# 150225_AriloTX_REV2_4_0_868MHZ.net
KiCad netlist of a schematic drawn in EAGLE
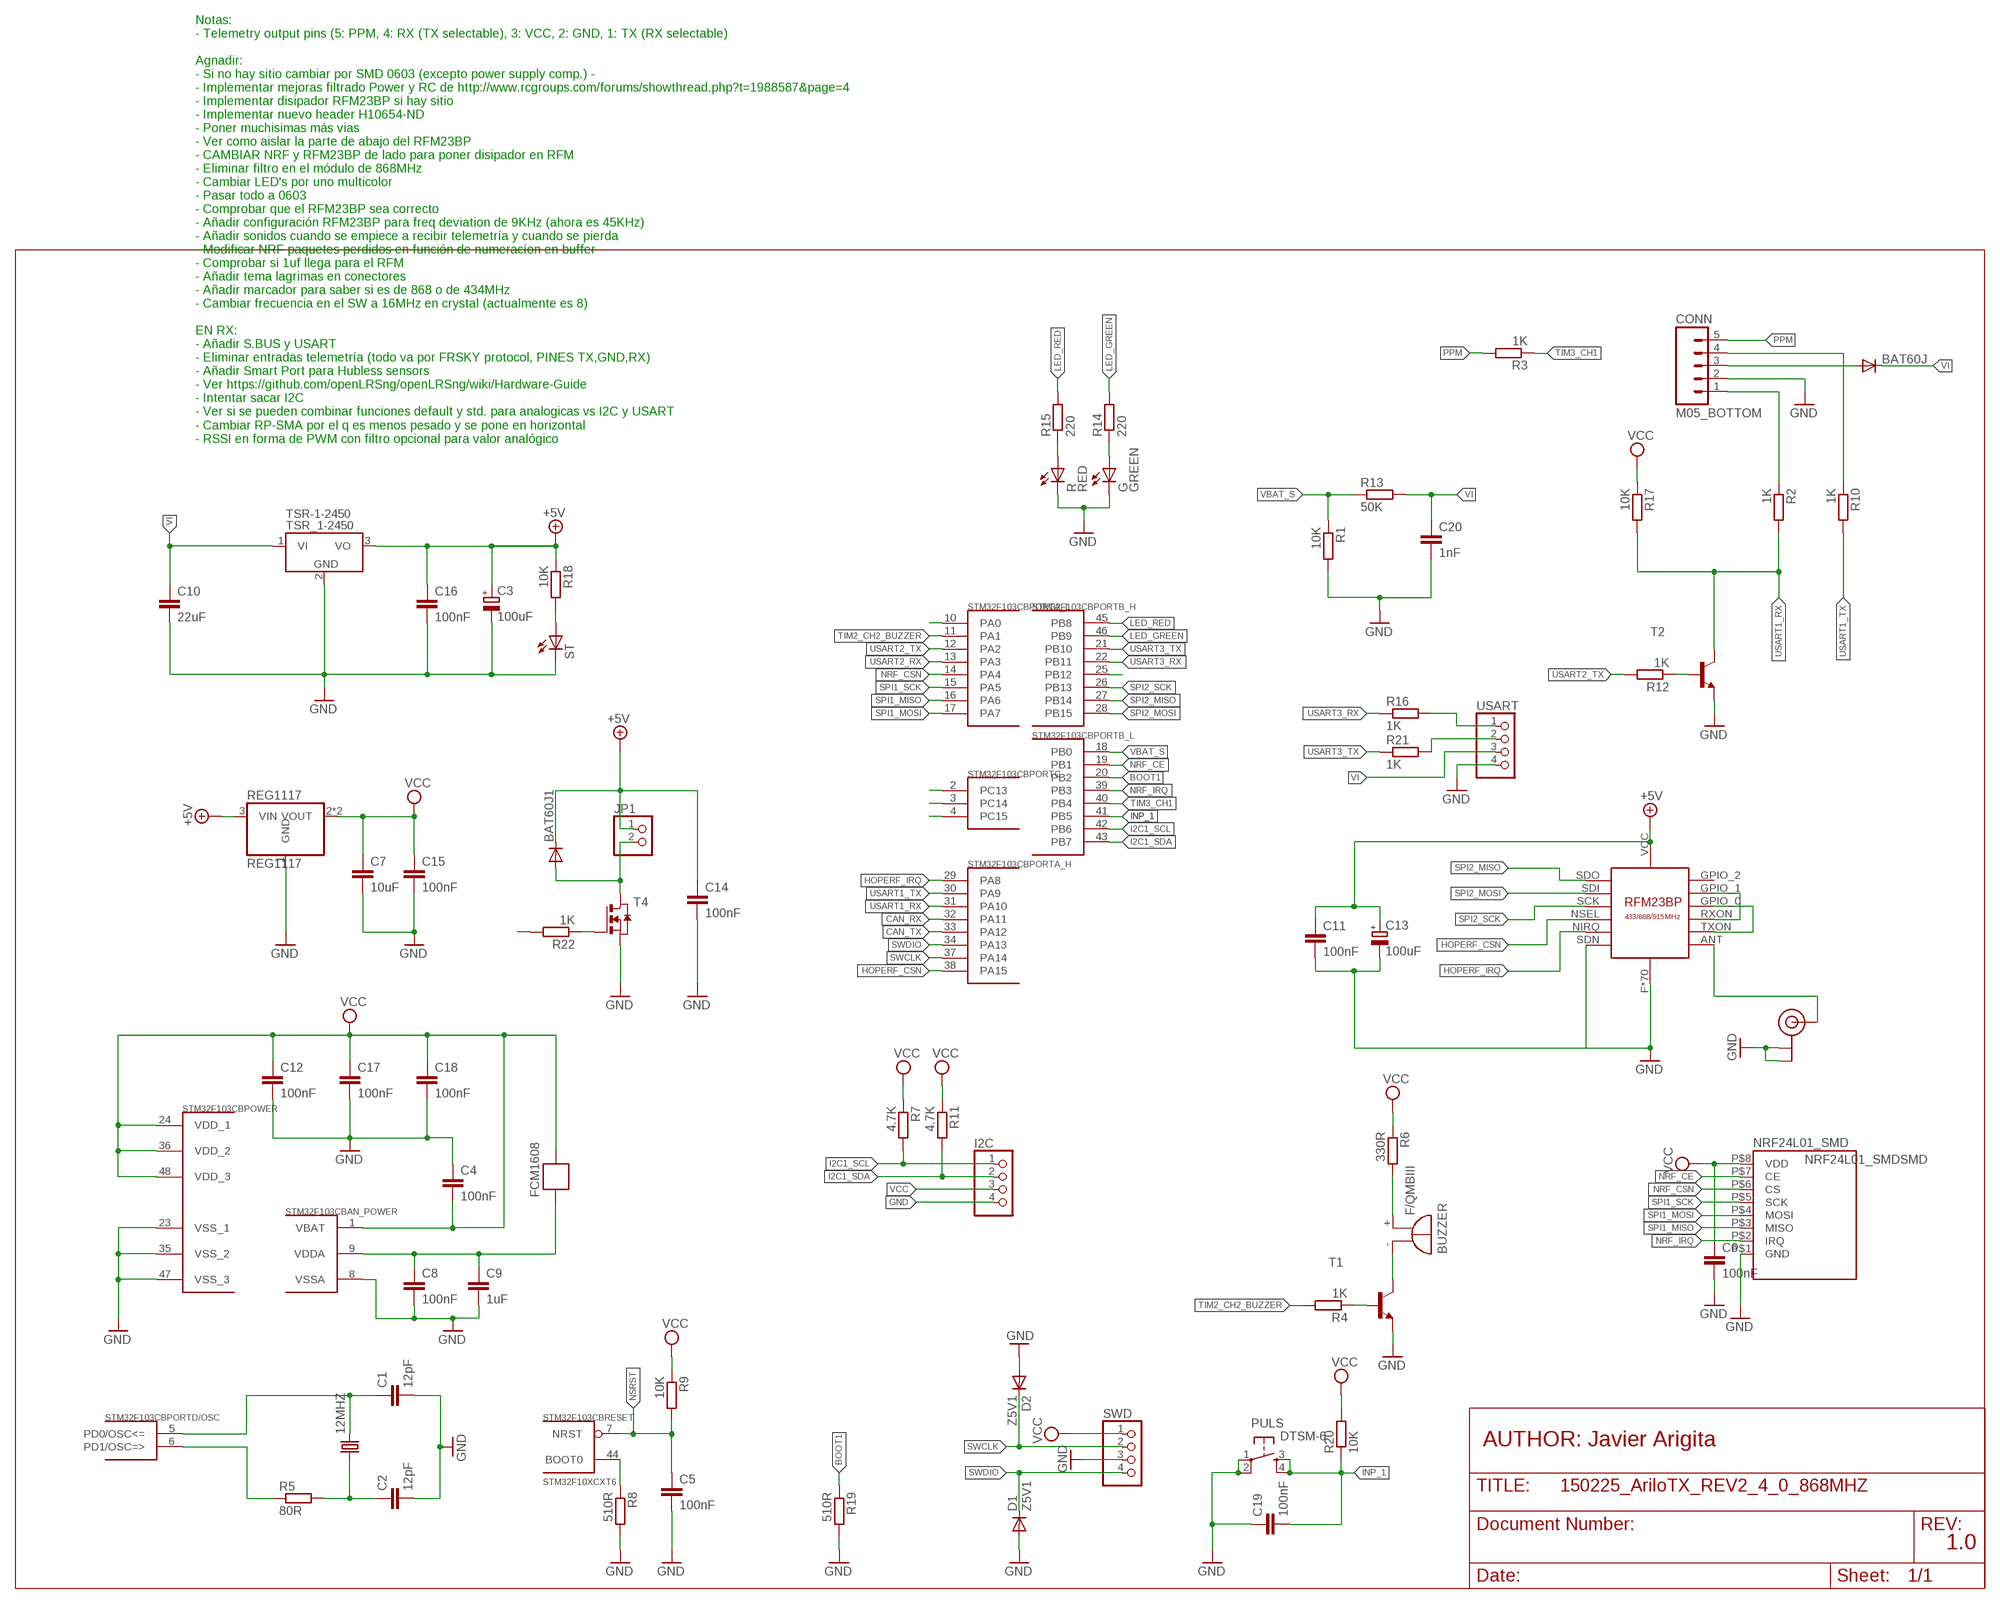
[diagram p0: schematic, sheet 1]

(export (version "E")
  (design (tool "Eeschema 10.0.6"))
  (components
    (comp (ref "12MHZ")
      (value "CRYSTAL5X3")
      (footprint "eagle-import:CRYSTAL-SMD-5X3")
      (libsource (lib "eagle-import") (part "CRYSTAL5X3"))
    )
    (comp (ref "BAT60J")
      (value "DIODE-SOD323-R")
      (footprint "eagle-import:SOD323-R")
      (libsource (lib "eagle-import") (part "DIODE-SOD323-R"))
    )
    (comp (ref "BAT60J1")
      (value "DIODE-SOD323-R")
      (footprint "eagle-import:SOD323-R")
      (libsource (lib "eagle-import") (part "DIODE-SOD323-R"))
    )
    (comp (ref "BUZZER")
      (value "F/QMBIII")
      (footprint "eagle-import:F_QMBIII")
      (libsource (lib "eagle-import") (part "F/QMBIII"))
    )
    (comp (ref "C1")
      (value "12pF")
      (footprint "eagle-import:C0603")
      (libsource (lib "eagle-import") (part "C-EUC0603"))
    )
    (comp (ref "C2")
      (value "12pF")
      (footprint "eagle-import:C0603")
      (libsource (lib "eagle-import") (part "C-EUC0603"))
    )
    (comp (ref "C3")
      (value "100uF")
      (footprint "eagle-import:SMC_B")
      (libsource (lib "eagle-import") (part "CPOL-EUSMCB"))
    )
    (comp (ref "C4")
      (value "100nF")
      (footprint "eagle-import:C0603")
      (libsource (lib "eagle-import") (part "C-EUC0603"))
    )
    (comp (ref "C5")
      (value "100nF")
      (footprint "eagle-import:C0603")
      (libsource (lib "eagle-import") (part "C-EUC0603"))
    )
    (comp (ref "C6")
      (value "100nF")
      (footprint "eagle-import:C0603")
      (libsource (lib "eagle-import") (part "C-EUC0603"))
    )
    (comp (ref "C7")
      (value "10uF")
      (footprint "eagle-import:C0805")
      (libsource (lib "eagle-import") (part "C-EUC0805"))
    )
    (comp (ref "C8")
      (value "100nF")
      (footprint "eagle-import:C0603")
      (libsource (lib "eagle-import") (part "C-EUC0603"))
    )
    (comp (ref "C9")
      (value "1uF")
      (footprint "eagle-import:C0603")
      (libsource (lib "eagle-import") (part "C-EUC0603"))
    )
    (comp (ref "C10")
      (value "22uF")
      (footprint "eagle-import:C3216")
      (libsource (lib "eagle-import") (part "resistor_C-EUC3216"))
    )
    (comp (ref "C11")
      (value "100nF")
      (footprint "eagle-import:C0603")
      (libsource (lib "eagle-import") (part "C-EUC0603"))
    )
    (comp (ref "C12")
      (value "100nF")
      (footprint "eagle-import:C0603")
      (libsource (lib "eagle-import") (part "C-EUC0603"))
    )
    (comp (ref "C13")
      (value "100uF")
      (footprint "eagle-import:SMC_B")
      (libsource (lib "eagle-import") (part "CPOL-EUSMCB"))
    )
    (comp (ref "C14")
      (value "100nF")
      (footprint "eagle-import:C0603")
      (libsource (lib "eagle-import") (part "C-EUC0603"))
    )
    (comp (ref "C15")
      (value "100nF")
      (footprint "eagle-import:C0603")
      (libsource (lib "eagle-import") (part "C-EUC0603"))
    )
    (comp (ref "C16")
      (value "100nF")
      (footprint "eagle-import:C0603")
      (libsource (lib "eagle-import") (part "C-EUC0603"))
    )
    (comp (ref "C17")
      (value "100nF")
      (footprint "eagle-import:C0603")
      (libsource (lib "eagle-import") (part "C-EUC0603"))
    )
    (comp (ref "C18")
      (value "100nF")
      (footprint "eagle-import:C0603")
      (libsource (lib "eagle-import") (part "C-EUC0603"))
    )
    (comp (ref "C19")
      (value "100nF")
      (footprint "eagle-import:C0603")
      (libsource (lib "eagle-import") (part "C-EUC0603"))
    )
    (comp (ref "C20")
      (value "1nF")
      (footprint "eagle-import:C0603")
      (libsource (lib "eagle-import") (part "C-EUC0603"))
    )
    (comp (ref "CONN")
      (value "M05_BOTTOM")
      (footprint "eagle-import:M05_BOTTOM")
      (libsource (lib "eagle-import") (part "M05_BOTTOM"))
    )
    (comp (ref "D1")
      (value "Z5V1")
      (footprint "eagle-import:SOD323-R")
      (libsource (lib "eagle-import") (part "DIODE-SOD323-R"))
    )
    (comp (ref "D2")
      (value "Z5V1")
      (footprint "eagle-import:SOD323-R")
      (libsource (lib "eagle-import") (part "DIODE-SOD323-R"))
    )
    (comp (ref "FCM1608")
      (value "FERRITE-BEAD")
      (footprint "eagle-import:R0603")
      (libsource (lib "eagle-import") (part "FERRITE-BEAD"))
    )
    (comp (ref "G")
      (value "GREEN")
      (footprint "eagle-import:CHIP-LED0603")
      (libsource (lib "eagle-import") (part "LEDCHIP-LED0603"))
    )
    (comp (ref "I2C")
      (value "PINHD-1X4")
      (footprint "eagle-import:1X04")
      (libsource (lib "eagle-import") (part "PINHD-1X4"))
    )
    (comp (ref "JP1")
      (value "PINHD-1X2")
      (footprint "eagle-import:1X02")
      (libsource (lib "eagle-import") (part "PINHD-1X2"))
    )
    (comp (ref "NRF24L01_SMD")
      (value "NRF24L01_SMDSMD")
      (footprint "eagle-import:NRF24L01_SMD")
      (libsource (lib "eagle-import") (part "NRF24L01_SMDSMD"))
    )
    (comp (ref "PULS")
      (value "DTSM-6")
      (footprint "eagle-import:DTSM-6")
      (libsource (lib "eagle-import") (part "DTSM-6"))
    )
    (comp (ref "R")
      (value "RED")
      (footprint "eagle-import:CHIP-LED0603")
      (libsource (lib "eagle-import") (part "LEDCHIP-LED0603"))
    )
    (comp (ref "R1")
      (value "10K")
      (footprint "eagle-import:R0603")
      (libsource (lib "eagle-import") (part "R-EU_R0603"))
    )
    (comp (ref "R2")
      (value "1K")
      (footprint "eagle-import:R0603")
      (libsource (lib "eagle-import") (part "R-EU_R0603"))
    )
    (comp (ref "R3")
      (value "1K")
      (footprint "eagle-import:R0603")
      (libsource (lib "eagle-import") (part "R-EU_R0603"))
    )
    (comp (ref "R4")
      (value "1K")
      (footprint "eagle-import:R0603")
      (libsource (lib "eagle-import") (part "R-EU_R0603"))
    )
    (comp (ref "R5")
      (value "80R")
      (footprint "eagle-import:R0603")
      (libsource (lib "eagle-import") (part "R-EU_R0603"))
    )
    (comp (ref "R6")
      (value "330R")
      (footprint "eagle-import:R0603")
      (libsource (lib "eagle-import") (part "R-EU_R0603"))
    )
    (comp (ref "R7")
      (value "4.7K")
      (footprint "eagle-import:R0603")
      (libsource (lib "eagle-import") (part "R-EU_R0603"))
    )
    (comp (ref "R8")
      (value "510R")
      (footprint "eagle-import:R0603")
      (libsource (lib "eagle-import") (part "R-EU_R0603"))
    )
    (comp (ref "R9")
      (value "10K")
      (footprint "eagle-import:R0603")
      (libsource (lib "eagle-import") (part "R-EU_R0603"))
    )
    (comp (ref "R10")
      (value "1K")
      (footprint "eagle-import:R0603")
      (libsource (lib "eagle-import") (part "R-EU_R0603"))
    )
    (comp (ref "R11")
      (value "4.7K")
      (footprint "eagle-import:R0603")
      (libsource (lib "eagle-import") (part "R-EU_R0603"))
    )
    (comp (ref "R12")
      (value "1K")
      (footprint "eagle-import:R0603")
      (libsource (lib "eagle-import") (part "R-EU_R0603"))
    )
    (comp (ref "R13")
      (value "50K")
      (footprint "eagle-import:R0603")
      (libsource (lib "eagle-import") (part "R-EU_R0603"))
    )
    (comp (ref "R14")
      (value "220")
      (footprint "eagle-import:R0603")
      (libsource (lib "eagle-import") (part "R-EU_R0603"))
    )
    (comp (ref "R15")
      (value "220")
      (footprint "eagle-import:R0603")
      (libsource (lib "eagle-import") (part "R-EU_R0603"))
    )
    (comp (ref "R16")
      (value "1K")
      (footprint "eagle-import:R0603")
      (libsource (lib "eagle-import") (part "R-EU_R0603"))
    )
    (comp (ref "R17")
      (value "10K")
      (footprint "eagle-import:R0603")
      (libsource (lib "eagle-import") (part "R-EU_R0603"))
    )
    (comp (ref "R18")
      (value "10K")
      (footprint "eagle-import:R0603")
      (libsource (lib "eagle-import") (part "R-EU_R0603"))
    )
    (comp (ref "R19")
      (value "510R")
      (footprint "eagle-import:R0603")
      (libsource (lib "eagle-import") (part "R-EU_R0603"))
    )
    (comp (ref "R20")
      (value "10K")
      (footprint "eagle-import:R0603")
      (libsource (lib "eagle-import") (part "R-EU_R0603"))
    )
    (comp (ref "R21")
      (value "1K")
      (footprint "eagle-import:R0603")
      (libsource (lib "eagle-import") (part "R-EU_R0603"))
    )
    (comp (ref "R22")
      (value "1K")
      (footprint "eagle-import:R0603")
      (libsource (lib "eagle-import") (part "R-EU_R0603"))
    )
    (comp (ref "REG1117")
      (value "REG1117")
      (footprint "eagle-import:SOT223")
      (libsource (lib "eagle-import") (part "REG1117"))
    )
    (comp (ref "ST")
      (value "LEDCHIP-LED0603")
      (footprint "eagle-import:CHIP-LED0603")
      (libsource (lib "eagle-import") (part "LEDCHIP-LED0603"))
    )
    (comp (ref "STM32F103CB")
      (value "STM32F10XCXT6")
      (footprint "eagle-import:TQFP48")
      (libsource (lib "eagle-import") (part "STM32F10XCXT6"))
    )
    (comp (ref "SWD")
      (value "PINHD-1X4")
      (footprint "eagle-import:1X04")
      (libsource (lib "eagle-import") (part "PINHD-1X4"))
    )
    (comp (ref "T1")
      (value "BC848-NPN-SOT23-BEC")
      (footprint "eagle-import:SOT23-BEC")
      (libsource (lib "eagle-import") (part "-NPN-SOT23-BECBC848"))
    )
    (comp (ref "T2")
      (value "BC848-NPN-SOT23-BEC")
      (footprint "eagle-import:SOT23-BEC")
      (libsource (lib "eagle-import") (part "-NPN-SOT23-BECBC848"))
    )
    (comp (ref "T4")
      (value "NMOSSOT23")
      (footprint "eagle-import:SOT-23")
      (libsource (lib "eagle-import") (part "NMOSSOT23"))
    )
    (comp (ref "TSR-1-2450")
      (value "TSR_1-2450")
      (footprint "eagle-import:TSR-1")
      (libsource (lib "eagle-import") (part "TSR_1-2450"))
    )
    (comp (ref "U$1")
      (value "RFM23BP")
      (footprint "eagle-import:RFM23BP")
      (libsource (lib "eagle-import") (part "RFM23BP"))
    )
    (comp (ref "U.FL")
      (value "U.FL")
      (footprint "eagle-import:U.FL")
      (libsource (lib "eagle-import") (part "U.FL"))
    )
    (comp (ref "USART")
      (value "PINHD-1X4")
      (footprint "eagle-import:1X04")
      (libsource (lib "eagle-import") (part "PINHD-1X4"))
    )
  )
  (nets
    (net (code "1") (name "+5V") (class "Default")
      (node (ref "BAT60J1") (pin "C") (pinfunction "C_C") (pintype "passive"))
      (node (ref "C11") (pin "1") (pinfunction "1_1") (pintype "passive"))
      (node (ref "C13") (pin "+") (pinfunction "+_+") (pintype "passive"))
      (node (ref "C14") (pin "1") (pinfunction "1_1") (pintype "passive"))
      (node (ref "C16") (pin "1") (pinfunction "1_1") (pintype "passive"))
      (node (ref "C3") (pin "+") (pinfunction "+_+") (pintype "passive"))
      (node (ref "JP1") (pin "1") (pinfunction "1_1") (pintype "passive"))
      (node (ref "R18") (pin "1") (pinfunction "1_1") (pintype "passive"))
      (node (ref "REG1117") (pin "3") (pinfunction "VIN_3") (pintype "input"))
      (node (ref "TSR-1-2450") (pin "3") (pinfunction "VO_3") (pintype "power_in"))
      (node (ref "U$1") (pin "VCC") (pinfunction "VCC_VCC") (pintype "power_in"))
    )
    (net (code "2") (name "BOOT1") (class "Default")
      (node (ref "R19") (pin "1") (pinfunction "1_1") (pintype "passive"))
      (node (ref "STM32F103CB") (pin "20") (pinfunction "PB2_20") (pintype "bidirectional"))
    )
    (net (code "3") (name "CAN_RX") (class "Default")
      (node (ref "STM32F103CB") (pin "32") (pinfunction "PA11_32") (pintype "bidirectional"))
    )
    (net (code "4") (name "CAN_TX") (class "Default")
      (node (ref "STM32F103CB") (pin "33") (pinfunction "PA12_33") (pintype "bidirectional"))
    )
    (net (code "5") (name "GND") (class "Default")
      (node (ref "C1") (pin "2") (pinfunction "2_2") (pintype "passive"))
      (node (ref "C10") (pin "2") (pinfunction "2_2") (pintype "passive"))
      (node (ref "C11") (pin "2") (pinfunction "2_2") (pintype "passive"))
      (node (ref "C12") (pin "2") (pinfunction "2_2") (pintype "passive"))
      (node (ref "C13") (pin "-") (pinfunction "-_-") (pintype "passive"))
      (node (ref "C14") (pin "2") (pinfunction "2_2") (pintype "passive"))
      (node (ref "C15") (pin "2") (pinfunction "2_2") (pintype "passive"))
      (node (ref "C16") (pin "2") (pinfunction "2_2") (pintype "passive"))
      (node (ref "C17") (pin "2") (pinfunction "2_2") (pintype "passive"))
      (node (ref "C18") (pin "2") (pinfunction "2_2") (pintype "passive"))
      (node (ref "C19") (pin "1") (pinfunction "1_1") (pintype "passive"))
      (node (ref "C2") (pin "2") (pinfunction "2_2") (pintype "passive"))
      (node (ref "C20") (pin "2") (pinfunction "2_2") (pintype "passive"))
      (node (ref "C3") (pin "-") (pinfunction "-_-") (pintype "passive"))
      (node (ref "C4") (pin "1") (pinfunction "1_1") (pintype "passive"))
      (node (ref "C5") (pin "2") (pinfunction "2_2") (pintype "passive"))
      (node (ref "C6") (pin "2") (pinfunction "2_2") (pintype "passive"))
      (node (ref "C7") (pin "2") (pinfunction "2_2") (pintype "passive"))
      (node (ref "C8") (pin "2") (pinfunction "2_2") (pintype "passive"))
      (node (ref "C9") (pin "2") (pinfunction "2_2") (pintype "passive"))
      (node (ref "CONN") (pin "2") (pinfunction "2_2") (pintype "passive"))
      (node (ref "D1") (pin "A") (pinfunction "A_A") (pintype "passive"))
      (node (ref "D2") (pin "A") (pinfunction "A_A") (pintype "passive"))
      (node (ref "G") (pin "C") (pinfunction "C_C") (pintype "passive"))
      (node (ref "I2C") (pin "4") (pinfunction "4_4") (pintype "passive"))
      (node (ref "NRF24L01_SMD") (pin "P$1") (pinfunction "GND_P$1") (pintype "power_in"))
      (node (ref "PULS") (pin "1") (pinfunction "1_1") (pintype "passive"))
      (node (ref "PULS") (pin "2") (pinfunction "2_2") (pintype "passive"))
      (node (ref "R") (pin "C") (pinfunction "C_C") (pintype "passive"))
      (node (ref "R1") (pin "2") (pinfunction "2_2") (pintype "passive"))
      (node (ref "R19") (pin "2") (pinfunction "2_2") (pintype "passive"))
      (node (ref "R8") (pin "2") (pinfunction "2_2") (pintype "passive"))
      (node (ref "REG1117") (pin "1") (pinfunction "GND_1") (pintype "power_in"))
      (node (ref "ST") (pin "C") (pinfunction "C_C") (pintype "passive"))
      (node (ref "STM32F103CB") (pin "23") (pinfunction "VSS_1_23") (pintype "power_in"))
      (node (ref "STM32F103CB") (pin "35") (pinfunction "VSS_2_35") (pintype "power_in"))
      (node (ref "STM32F103CB") (pin "47") (pinfunction "VSS_3_47") (pintype "power_in"))
      (node (ref "STM32F103CB") (pin "8") (pinfunction "VSSA_8") (pintype "power_in"))
      (node (ref "SWD") (pin "3") (pinfunction "3_3") (pintype "passive"))
      (node (ref "T1") (pin "E") (pinfunction "E_E") (pintype "passive"))
      (node (ref "T2") (pin "E") (pinfunction "E_E") (pintype "passive"))
      (node (ref "T4") (pin "2") (pinfunction "S_2") (pintype "passive"))
      (node (ref "TSR-1-2450") (pin "2") (pinfunction "GND_2") (pintype "power_in"))
      (node (ref "U$1") (pin "F") (pinfunction "GND_F") (pintype "power_in"))
      (node (ref "U$1") (pin "F1") (pinfunction "GND_F1") (pintype "power_in"))
      (node (ref "U$1") (pin "F10") (pinfunction "GND_F10") (pintype "power_in"))
      (node (ref "U$1") (pin "F11") (pinfunction "GND_F11") (pintype "power_in"))
      (node (ref "U$1") (pin "F12") (pinfunction "GND_F12") (pintype "power_in"))
      (node (ref "U$1") (pin "F13") (pinfunction "GND_F13") (pintype "power_in"))
      (node (ref "U$1") (pin "F14") (pinfunction "GND_F14") (pintype "power_in"))
      (node (ref "U$1") (pin "F15") (pinfunction "GND_F15") (pintype "power_in"))
      (node (ref "U$1") (pin "F16") (pinfunction "GND_F16") (pintype "power_in"))
      (node (ref "U$1") (pin "F17") (pinfunction "GND_F17") (pintype "power_in"))
      (node (ref "U$1") (pin "F18") (pinfunction "GND_F18") (pintype "power_in"))
      (node (ref "U$1") (pin "F19") (pinfunction "GND_F19") (pintype "power_in"))
      (node (ref "U$1") (pin "F2") (pinfunction "GND_F2") (pintype "power_in"))
      (node (ref "U$1") (pin "F20") (pinfunction "GND_F20") (pintype "power_in"))
      (node (ref "U$1") (pin "F21") (pinfunction "GND_F21") (pintype "power_in"))
      (node (ref "U$1") (pin "F22") (pinfunction "GND_F22") (pintype "power_in"))
      (node (ref "U$1") (pin "F23") (pinfunction "GND_F23") (pintype "power_in"))
      (node (ref "U$1") (pin "F24") (pinfunction "GND_F24") (pintype "power_in"))
      (node (ref "U$1") (pin "F25") (pinfunction "GND_F25") (pintype "power_in"))
      (node (ref "U$1") (pin "F26") (pinfunction "GND_F26") (pintype "power_in"))
      (node (ref "U$1") (pin "F27") (pinfunction "GND_F27") (pintype "power_in"))
      (node (ref "U$1") (pin "F28") (pinfunction "GND_F28") (pintype "power_in"))
      (node (ref "U$1") (pin "F29") (pinfunction "GND_F29") (pintype "power_in"))
      (node (ref "U$1") (pin "F3") (pinfunction "GND_F3") (pintype "power_in"))
      (node (ref "U$1") (pin "F30") (pinfunction "GND_F30") (pintype "power_in"))
      (node (ref "U$1") (pin "F31") (pinfunction "GND_F31") (pintype "power_in"))
      (node (ref "U$1") (pin "F32") (pinfunction "GND_F32") (pintype "power_in"))
      (node (ref "U$1") (pin "F33") (pinfunction "GND_F33") (pintype "power_in"))
      (node (ref "U$1") (pin "F34") (pinfunction "GND_F34") (pintype "power_in"))
      (node (ref "U$1") (pin "F35") (pinfunction "GND_F35") (pintype "power_in"))
      (node (ref "U$1") (pin "F36") (pinfunction "GND_F36") (pintype "power_in"))
      (node (ref "U$1") (pin "F37") (pinfunction "GND_F37") (pintype "power_in"))
      (node (ref "U$1") (pin "F38") (pinfunction "GND_F38") (pintype "power_in"))
      (node (ref "U$1") (pin "F39") (pinfunction "GND_F39") (pintype "power_in"))
      (node (ref "U$1") (pin "F4") (pinfunction "GND_F4") (pintype "power_in"))
      (node (ref "U$1") (pin "F40") (pinfunction "GND_F40") (pintype "power_in"))
      (node (ref "U$1") (pin "F41") (pinfunction "GND_F41") (pintype "power_in"))
      (node (ref "U$1") (pin "F42") (pinfunction "GND_F42") (pintype "power_in"))
      (node (ref "U$1") (pin "F43") (pinfunction "GND_F43") (pintype "power_in"))
      (node (ref "U$1") (pin "F44") (pinfunction "GND_F44") (pintype "power_in"))
      (node (ref "U$1") (pin "F45") (pinfunction "GND_F45") (pintype "power_in"))
      (node (ref "U$1") (pin "F46") (pinfunction "GND_F46") (pintype "power_in"))
      (node (ref "U$1") (pin "F47") (pinfunction "GND_F47") (pintype "power_in"))
      (node (ref "U$1") (pin "F48") (pinfunction "GND_F48") (pintype "power_in"))
      (node (ref "U$1") (pin "F49") (pinfunction "GND_F49") (pintype "power_in"))
      (node (ref "U$1") (pin "F5") (pinfunction "GND_F5") (pintype "power_in"))
      (node (ref "U$1") (pin "F50") (pinfunction "GND_F50") (pintype "power_in"))
      (node (ref "U$1") (pin "F51") (pinfunction "GND_F51") (pintype "power_in"))
      (node (ref "U$1") (pin "F52") (pinfunction "GND_F52") (pintype "power_in"))
      (node (ref "U$1") (pin "F53") (pinfunction "GND_F53") (pintype "power_in"))
      (node (ref "U$1") (pin "F54") (pinfunction "GND_F54") (pintype "power_in"))
      (node (ref "U$1") (pin "F55") (pinfunction "GND_F55") (pintype "power_in"))
      (node (ref "U$1") (pin "F56") (pinfunction "GND_F56") (pintype "power_in"))
      (node (ref "U$1") (pin "F57") (pinfunction "GND_F57") (pintype "power_in"))
      (node (ref "U$1") (pin "F58") (pinfunction "GND_F58") (pintype "power_in"))
      (node (ref "U$1") (pin "F59") (pinfunction "GND_F59") (pintype "power_in"))
      (node (ref "U$1") (pin "F6") (pinfunction "GND_F6") (pintype "power_in"))
      (node (ref "U$1") (pin "F60") (pinfunction "GND_F60") (pintype "power_in"))
      (node (ref "U$1") (pin "F61") (pinfunction "GND_F61") (pintype "power_in"))
      (node (ref "U$1") (pin "F62") (pinfunction "GND_F62") (pintype "power_in"))
      (node (ref "U$1") (pin "F63") (pinfunction "GND_F63") (pintype "power_in"))
      (node (ref "U$1") (pin "F64") (pinfunction "GND_F64") (pintype "power_in"))
      (node (ref "U$1") (pin "F65") (pinfunction "GND_F65") (pintype "power_in"))
      (node (ref "U$1") (pin "F7") (pinfunction "GND_F7") (pintype "power_in"))
      (node (ref "U$1") (pin "F8") (pinfunction "GND_F8") (pintype "power_in"))
      (node (ref "U$1") (pin "F9") (pinfunction "GND_F9") (pintype "power_in"))
      (node (ref "U$1") (pin "GND1") (pinfunction "GND_GND1") (pintype "power_in"))
      (node (ref "U$1") (pin "GND2") (pinfunction "GND_GND2") (pintype "power_in"))
      (node (ref "U$1") (pin "GND3") (pinfunction "GND_GND3") (pintype "power_in"))
      (node (ref "U$1") (pin "GND_HEAT") (pinfunction "GND_GND_HEAT") (pintype "power_in"))
      (node (ref "U$1") (pin "SDN") (pinfunction "SDN_SDN") (pintype "bidirectional"))
      (node (ref "U.FL") (pin "P$1") (pinfunction "GND_P$1") (pintype "bidirectional"))
      (node (ref "U.FL") (pin "P$2") (pinfunction "GND_P$2") (pintype "bidirectional"))
      (node (ref "USART") (pin "4") (pinfunction "4_4") (pintype "passive"))
    )
    (net (code "6") (name "HOPERF_CSN") (class "Default")
      (node (ref "STM32F103CB") (pin "38") (pinfunction "PA15_38") (pintype "bidirectional"))
      (node (ref "U$1") (pin "NSEL") (pinfunction "NSEL_NSEL") (pintype "bidirectional"))
    )
    (net (code "7") (name "HOPERF_IRQ") (class "Default")
      (node (ref "STM32F103CB") (pin "29") (pinfunction "PA8_29") (pintype "bidirectional"))
      (node (ref "U$1") (pin "NIRQ") (pinfunction "NIRQ_NIRQ") (pintype "bidirectional"))
    )
    (net (code "8") (name "I2C1_SCL") (class "Default")
      (node (ref "I2C") (pin "1") (pinfunction "1_1") (pintype "passive"))
      (node (ref "R7") (pin "2") (pinfunction "2_2") (pintype "passive"))
      (node (ref "STM32F103CB") (pin "42") (pinfunction "PB6_42") (pintype "bidirectional"))
    )
    (net (code "9") (name "I2C1_SDA") (class "Default")
      (node (ref "I2C") (pin "2") (pinfunction "2_2") (pintype "passive"))
      (node (ref "R11") (pin "2") (pinfunction "2_2") (pintype "passive"))
      (node (ref "STM32F103CB") (pin "43") (pinfunction "PB7_43") (pintype "bidirectional"))
    )
    (net (code "10") (name "INP_1") (class "Default")
      (node (ref "C19") (pin "2") (pinfunction "2_2") (pintype "passive"))
      (node (ref "PULS") (pin "3") (pinfunction "3_3") (pintype "passive"))
      (node (ref "PULS") (pin "4") (pinfunction "4_4") (pintype "passive"))
      (node (ref "R20") (pin "1") (pinfunction "1_1") (pintype "passive"))
      (node (ref "STM32F103CB") (pin "41") (pinfunction "PB5_41") (pintype "bidirectional"))
    )
    (net (code "11") (name "LED_GREEN") (class "Default")
      (node (ref "R14") (pin "2") (pinfunction "2_2") (pintype "passive"))
      (node (ref "STM32F103CB") (pin "46") (pinfunction "PB9_46") (pintype "bidirectional"))
    )
    (net (code "12") (name "LED_RED") (class "Default")
      (node (ref "R15") (pin "2") (pinfunction "2_2") (pintype "passive"))
      (node (ref "STM32F103CB") (pin "45") (pinfunction "PB8_45") (pintype "bidirectional"))
    )
    (net (code "13") (name "NRF_CE") (class "Default")
      (node (ref "NRF24L01_SMD") (pin "P$7") (pinfunction "CE_P$7") (pintype "input"))
      (node (ref "STM32F103CB") (pin "19") (pinfunction "PB1_19") (pintype "bidirectional"))
    )
    (net (code "14") (name "NRF_CSN") (class "Default")
      (node (ref "NRF24L01_SMD") (pin "P$6") (pinfunction "CS_P$6") (pintype "input"))
      (node (ref "STM32F103CB") (pin "14") (pinfunction "PA4_14") (pintype "bidirectional"))
    )
    (net (code "15") (name "NRF_IRQ") (class "Default")
      (node (ref "NRF24L01_SMD") (pin "P$2") (pinfunction "IRQ_P$2") (pintype "output"))
      (node (ref "STM32F103CB") (pin "39") (pinfunction "PB3_39") (pintype "bidirectional"))
    )
    (net (code "16") (name "NSRST") (class "Default")
      (node (ref "C5") (pin "1") (pinfunction "1_1") (pintype "passive"))
      (node (ref "R9") (pin "2") (pinfunction "2_2") (pintype "passive"))
      (node (ref "STM32F103CB") (pin "7") (pinfunction "NRST_7") (pintype "input"))
    )
    (net (code "17") (name "Net-(12MHZ-2)") (class "Default")
      (node (ref "12MHZ") (pin "3") (pinfunction "2_3") (pintype "passive"))
      (node (ref "C1") (pin "1") (pinfunction "1_1") (pintype "passive"))
      (node (ref "STM32F103CB") (pin "5") (pinfunction "PD0/OSC<=_5") (pintype "bidirectional"))
    )
    (net (code "18") (name "Net-(12MHZ-Pad1)") (class "Default")
      (node (ref "12MHZ") (pin "1") (pinfunction "1_1") (pintype "passive"))
      (node (ref "C2") (pin "1") (pinfunction "1_1") (pintype "passive"))
      (node (ref "R5") (pin "2") (pinfunction "2_2") (pintype "passive"))
    )
    (net (code "19") (name "Net-(BAT60J-PadA)") (class "Default")
      (node (ref "BAT60J") (pin "A") (pinfunction "A_A") (pintype "passive"))
      (node (ref "CONN") (pin "3") (pinfunction "3_3") (pintype "passive"))
    )
    (net (code "20") (name "Net-(BUZZER-+)") (class "Default")
      (node (ref "BUZZER") (pin "-") (pinfunction "+_-") (pintype "passive"))
      (node (ref "T1") (pin "C") (pinfunction "C_C") (pintype "passive"))
    )
    (net (code "21") (name "Net-(BUZZER--)") (class "Default")
      (node (ref "BUZZER") (pin "+") (pinfunction "-_+") (pintype "passive"))
      (node (ref "R6") (pin "2") (pinfunction "2_2") (pintype "passive"))
    )
    (net (code "22") (name "Net-(CONN-Pad1)") (class "Default")
      (node (ref "CONN") (pin "1") (pinfunction "1_1") (pintype "passive"))
      (node (ref "R2") (pin "1") (pinfunction "1_1") (pintype "passive"))
    )
    (net (code "23") (name "Net-(CONN-Pad4)") (class "Default")
      (node (ref "CONN") (pin "4") (pinfunction "4_4") (pintype "passive"))
      (node (ref "R10") (pin "1") (pinfunction "1_1") (pintype "passive"))
    )
    (net (code "24") (name "Net-(FCM1608-P$2)") (class "Default")
      (node (ref "C8") (pin "1") (pinfunction "1_1") (pintype "passive"))
      (node (ref "C9") (pin "1") (pinfunction "1_1") (pintype "passive"))
      (node (ref "FCM1608") (pin "2") (pinfunction "P$2_2") (pintype "bidirectional"))
      (node (ref "STM32F103CB") (pin "9") (pinfunction "VDDA_9") (pintype "power_in"))
    )
    (net (code "25") (name "Net-(G-PadA)") (class "Default")
      (node (ref "G") (pin "A") (pinfunction "A_A") (pintype "passive"))
      (node (ref "R14") (pin "1") (pinfunction "1_1") (pintype "passive"))
    )
    (net (code "26") (name "Net-(R-PadA)") (class "Default")
      (node (ref "R") (pin "A") (pinfunction "A_A") (pintype "passive"))
      (node (ref "R15") (pin "1") (pinfunction "1_1") (pintype "passive"))
    )
    (net (code "27") (name "Net-(R4-Pad1)") (class "Default")
      (node (ref "R4") (pin "1") (pinfunction "1_1") (pintype "passive"))
      (node (ref "T1") (pin "B") (pinfunction "B_B") (pintype "passive"))
    )
    (net (code "28") (name "Net-(R12-Pad1)") (class "Default")
      (node (ref "R12") (pin "1") (pinfunction "1_1") (pintype "passive"))
      (node (ref "T2") (pin "B") (pinfunction "B_B") (pintype "passive"))
    )
    (net (code "29") (name "Net-(R16-Pad2)") (class "Default")
      (node (ref "R16") (pin "2") (pinfunction "2_2") (pintype "passive"))
      (node (ref "USART") (pin "1") (pinfunction "1_1") (pintype "passive"))
    )
    (net (code "30") (name "Net-(R18-Pad2)") (class "Default")
      (node (ref "R18") (pin "2") (pinfunction "2_2") (pintype "passive"))
      (node (ref "ST") (pin "A") (pinfunction "A_A") (pintype "passive"))
    )
    (net (code "31") (name "Net-(R21-Pad2)") (class "Default")
      (node (ref "R21") (pin "2") (pinfunction "2_2") (pintype "passive"))
      (node (ref "USART") (pin "2") (pinfunction "2_2") (pintype "passive"))
    )
    (net (code "32") (name "Net-(STM32F103CBG-PD1{slash}OSC=>)") (class "Default")
      (node (ref "R5") (pin "1") (pinfunction "1_1") (pintype "passive"))
      (node (ref "STM32F103CB") (pin "6") (pinfunction "PD1/OSC=>_6") (pintype "bidirectional"))
    )
    (net (code "33") (name "Net-(STM32F103CBI-BOOT0)") (class "Default")
      (node (ref "R8") (pin "1") (pinfunction "1_1") (pintype "passive"))
      (node (ref "STM32F103CB") (pin "44") (pinfunction "BOOT0_44") (pintype "input"))
    )
    (net (code "34") (name "Net-(T4-D)") (class "Default")
      (node (ref "BAT60J1") (pin "A") (pinfunction "A_A") (pintype "passive"))
      (node (ref "JP1") (pin "2") (pinfunction "2_2") (pintype "passive"))
      (node (ref "T4") (pin "1") (pinfunction "D_1") (pintype "passive"))
    )
    (net (code "35") (name "Net-(T4-G)") (class "Default")
      (node (ref "R22") (pin "1") (pinfunction "1_1") (pintype "passive"))
      (node (ref "T4") (pin "3") (pinfunction "G_3") (pintype "passive"))
    )
    (net (code "36") (name "Net-(U$1-PadGPIO_0)") (class "Default")
      (node (ref "U$1") (pin "GPIO_0") (pinfunction "GPIO_0_GPIO_0") (pintype "bidirectional"))
      (node (ref "U$1") (pin "TXON") (pinfunction "TXON_TXON") (pintype "bidirectional"))
    )
    (net (code "37") (name "Net-(U$1-PadGPIO_1)") (class "Default")
      (node (ref "U$1") (pin "GPIO_1") (pinfunction "GPIO_1_GPIO_1") (pintype "bidirectional"))
      (node (ref "U$1") (pin "RXON") (pinfunction "RXON_RXON") (pintype "bidirectional"))
    )
    (net (code "38") (name "Net-(U.FL-SIGNAL)") (class "Default")
      (node (ref "U$1") (pin "ANT") (pinfunction "ANT_ANT") (pintype "bidirectional"))
      (node (ref "U.FL") (pin "P$3") (pinfunction "SIGNAL_P$3") (pintype "bidirectional"))
    )
    (net (code "39") (name "PPM") (class "Default")
      (node (ref "CONN") (pin "5") (pinfunction "5_5") (pintype "passive"))
      (node (ref "R3") (pin "2") (pinfunction "2_2") (pintype "passive"))
    )
    (net (code "40") (name "SPI1_MISO") (class "Default")
      (node (ref "NRF24L01_SMD") (pin "P$3") (pinfunction "MISO_P$3") (pintype "output"))
      (node (ref "STM32F103CB") (pin "16") (pinfunction "PA6_16") (pintype "bidirectional"))
    )
    (net (code "41") (name "SPI1_MOSI") (class "Default")
      (node (ref "NRF24L01_SMD") (pin "P$4") (pinfunction "MOSI_P$4") (pintype "input"))
      (node (ref "STM32F103CB") (pin "17") (pinfunction "PA7_17") (pintype "bidirectional"))
    )
    (net (code "42") (name "SPI1_SCK") (class "Default")
      (node (ref "NRF24L01_SMD") (pin "P$5") (pinfunction "SCK_P$5") (pintype "input"))
      (node (ref "STM32F103CB") (pin "15") (pinfunction "PA5_15") (pintype "bidirectional"))
    )
    (net (code "43") (name "SPI2_MISO") (class "Default")
      (node (ref "STM32F103CB") (pin "27") (pinfunction "PB14_27") (pintype "bidirectional"))
      (node (ref "U$1") (pin "SDO") (pinfunction "SDO_SDO") (pintype "bidirectional"))
    )
    (net (code "44") (name "SPI2_MOSI") (class "Default")
      (node (ref "STM32F103CB") (pin "28") (pinfunction "PB15_28") (pintype "bidirectional"))
      (node (ref "U$1") (pin "SDI") (pinfunction "SDI_SDI") (pintype "bidirectional"))
    )
    (net (code "45") (name "SPI2_SCK") (class "Default")
      (node (ref "STM32F103CB") (pin "26") (pinfunction "PB13_26") (pintype "bidirectional"))
      (node (ref "U$1") (pin "SCK") (pinfunction "SCK_SCK") (pintype "bidirectional"))
    )
    (net (code "46") (name "SWCLK") (class "Default")
      (node (ref "D2") (pin "C") (pinfunction "C_C") (pintype "passive"))
      (node (ref "STM32F103CB") (pin "37") (pinfunction "PA14_37") (pintype "bidirectional"))
      (node (ref "SWD") (pin "2") (pinfunction "2_2") (pintype "passive"))
    )
    (net (code "47") (name "SWDIO") (class "Default")
      (node (ref "D1") (pin "C") (pinfunction "C_C") (pintype "passive"))
      (node (ref "STM32F103CB") (pin "34") (pinfunction "PA13_34") (pintype "bidirectional"))
      (node (ref "SWD") (pin "4") (pinfunction "4_4") (pintype "passive"))
    )
    (net (code "48") (name "TIM2_CH2_BUZZER") (class "Default")
      (node (ref "R4") (pin "2") (pinfunction "2_2") (pintype "passive"))
      (node (ref "STM32F103CB") (pin "11") (pinfunction "PA1_11") (pintype "bidirectional"))
    )
    (net (code "49") (name "TIM3_CH1") (class "Default")
      (node (ref "R3") (pin "1") (pinfunction "1_1") (pintype "passive"))
      (node (ref "STM32F103CB") (pin "40") (pinfunction "PB4_40") (pintype "bidirectional"))
    )
    (net (code "50") (name "USART1_RX") (class "Default")
      (node (ref "R17") (pin "2") (pinfunction "2_2") (pintype "passive"))
      (node (ref "R2") (pin "2") (pinfunction "2_2") (pintype "passive"))
      (node (ref "STM32F103CB") (pin "31") (pinfunction "PA10_31") (pintype "bidirectional"))
      (node (ref "T2") (pin "C") (pinfunction "C_C") (pintype "passive"))
    )
    (net (code "51") (name "USART1_TX") (class "Default")
      (node (ref "R10") (pin "2") (pinfunction "2_2") (pintype "passive"))
      (node (ref "STM32F103CB") (pin "30") (pinfunction "PA9_30") (pintype "bidirectional"))
    )
    (net (code "52") (name "USART2_RX") (class "Default")
      (node (ref "STM32F103CB") (pin "13") (pinfunction "PA3_13") (pintype "bidirectional"))
    )
    (net (code "53") (name "USART2_TX") (class "Default")
      (node (ref "R12") (pin "2") (pinfunction "2_2") (pintype "passive"))
      (node (ref "STM32F103CB") (pin "12") (pinfunction "PA2_12") (pintype "bidirectional"))
    )
    (net (code "54") (name "USART3_RX") (class "Default")
      (node (ref "R16") (pin "1") (pinfunction "1_1") (pintype "passive"))
      (node (ref "STM32F103CB") (pin "22") (pinfunction "PB11_22") (pintype "bidirectional"))
    )
    (net (code "55") (name "USART3_TX") (class "Default")
      (node (ref "R21") (pin "1") (pinfunction "1_1") (pintype "passive"))
      (node (ref "STM32F103CB") (pin "21") (pinfunction "PB10_21") (pintype "bidirectional"))
    )
    (net (code "56") (name "VBAT_S") (class "Default")
      (node (ref "R1") (pin "1") (pinfunction "1_1") (pintype "passive"))
      (node (ref "R13") (pin "1") (pinfunction "1_1") (pintype "passive"))
      (node (ref "STM32F103CB") (pin "18") (pinfunction "PB0_18") (pintype "bidirectional"))
    )
    (net (code "57") (name "VCC") (class "Default")
      (node (ref "C12") (pin "1") (pinfunction "1_1") (pintype "passive"))
      (node (ref "C15") (pin "1") (pinfunction "1_1") (pintype "passive"))
      (node (ref "C17") (pin "1") (pinfunction "1_1") (pintype "passive"))
      (node (ref "C18") (pin "1") (pinfunction "1_1") (pintype "passive"))
      (node (ref "C4") (pin "2") (pinfunction "2_2") (pintype "passive"))
      (node (ref "C6") (pin "1") (pinfunction "1_1") (pintype "passive"))
      (node (ref "C7") (pin "1") (pinfunction "1_1") (pintype "passive"))
      (node (ref "FCM1608") (pin "1") (pinfunction "P$1_1") (pintype "bidirectional"))
      (node (ref "I2C") (pin "3") (pinfunction "3_3") (pintype "passive"))
      (node (ref "NRF24L01_SMD") (pin "P$8") (pinfunction "VDD_P$8") (pintype "bidirectional"))
      (node (ref "R11") (pin "1") (pinfunction "1_1") (pintype "passive"))
      (node (ref "R17") (pin "1") (pinfunction "1_1") (pintype "passive"))
      (node (ref "R20") (pin "2") (pinfunction "2_2") (pintype "passive"))
      (node (ref "R6") (pin "1") (pinfunction "1_1") (pintype "passive"))
      (node (ref "R7") (pin "1") (pinfunction "1_1") (pintype "passive"))
      (node (ref "R9") (pin "1") (pinfunction "1_1") (pintype "passive"))
      (node (ref "REG1117") (pin "2") (pinfunction "VOUT_2") (pintype "power_in"))
      (node (ref "REG1117") (pin "4") (pinfunction "VOUT_4") (pintype "power_in"))
      (node (ref "STM32F103CB") (pin "1") (pinfunction "VBAT_1") (pintype "power_in"))
      (node (ref "STM32F103CB") (pin "24") (pinfunction "VDD_1_24") (pintype "power_in"))
      (node (ref "STM32F103CB") (pin "36") (pinfunction "VDD_2_36") (pintype "power_in"))
      (node (ref "STM32F103CB") (pin "48") (pinfunction "VDD_3_48") (pintype "power_in"))
      (node (ref "SWD") (pin "1") (pinfunction "1_1") (pintype "passive"))
    )
    (net (code "58") (name "VI") (class "Default")
      (node (ref "BAT60J") (pin "C") (pinfunction "C_C") (pintype "passive"))
      (node (ref "C10") (pin "1") (pinfunction "1_1") (pintype "passive"))
      (node (ref "C20") (pin "1") (pinfunction "1_1") (pintype "passive"))
      (node (ref "R13") (pin "2") (pinfunction "2_2") (pintype "passive"))
      (node (ref "TSR-1-2450") (pin "1") (pinfunction "VI_1") (pintype "power_in"))
      (node (ref "USART") (pin "3") (pinfunction "3_3") (pintype "passive"))
    )
    (net (code "59") (name "unconnected-(R22-Pad2)") (class "Default")
      (node (ref "R22") (pin "2") (pinfunction "2_2") (pintype "passive"))
    )
    (net (code "60") (name "unconnected-(STM32F103CBC-PA0-Pad10)") (class "Default")
      (node (ref "STM32F103CB") (pin "10") (pinfunction "PA0_10") (pintype "bidirectional"))
    )
    (net (code "61") (name "unconnected-(STM32F103CBD-PB12-Pad25)") (class "Default")
      (node (ref "STM32F103CB") (pin "25") (pinfunction "PB12_25") (pintype "bidirectional"))
    )
    (net (code "62") (name "unconnected-(STM32F103CBF-PC13-Pad2)") (class "Default")
      (node (ref "STM32F103CB") (pin "2") (pinfunction "PC13_2") (pintype "bidirectional"))
    )
    (net (code "63") (name "unconnected-(STM32F103CBF-PC14-Pad3)") (class "Default")
      (node (ref "STM32F103CB") (pin "3") (pinfunction "PC14_3") (pintype "bidirectional"))
    )
    (net (code "64") (name "unconnected-(STM32F103CBF-PC15-Pad4)") (class "Default")
      (node (ref "STM32F103CB") (pin "4") (pinfunction "PC15_4") (pintype "bidirectional"))
    )
    (net (code "65") (name "unconnected-(U$1-PadGPIO_2)") (class "Default")
      (node (ref "U$1") (pin "GPIO_2") (pinfunction "GPIO_2_GPIO_2") (pintype "bidirectional"))
    )
  )
)
